# pressure_temp_uv.net
KiCad netlist of a schematic drawn in Altium Designer
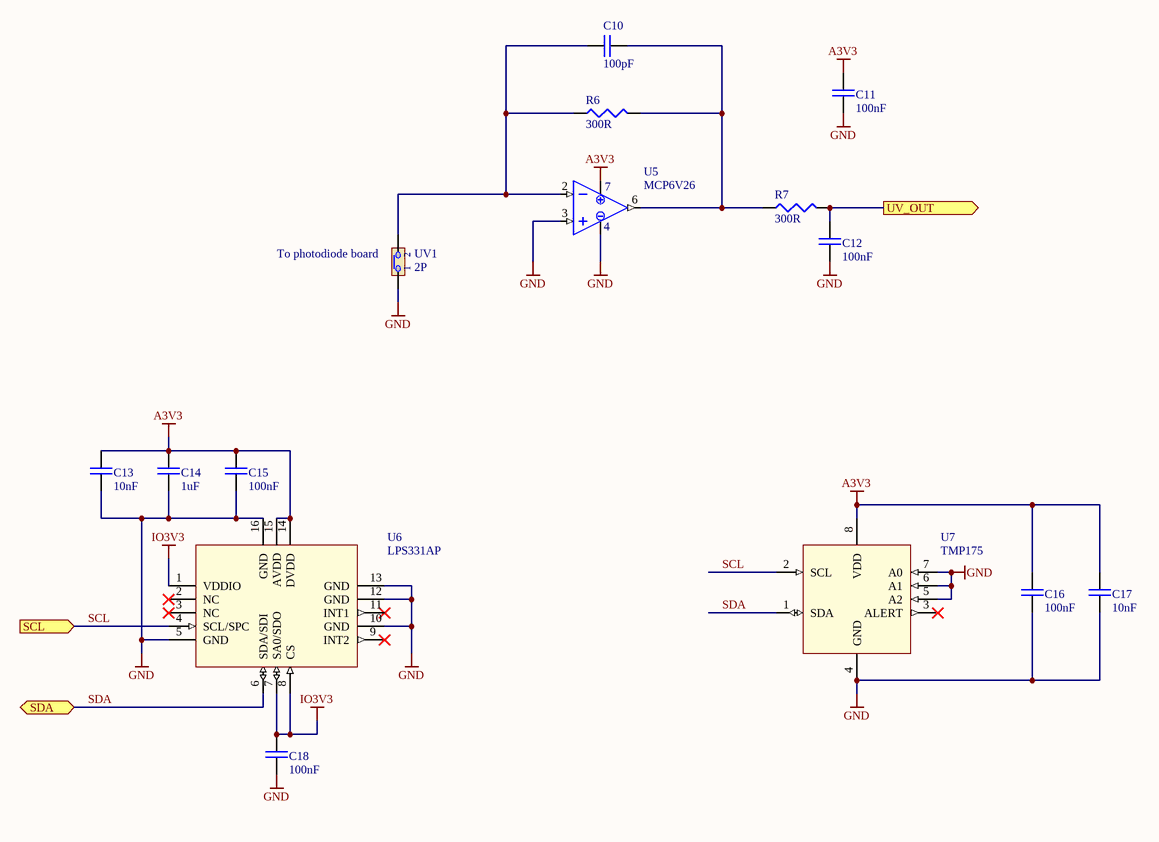
[diagram p0: pressure_temp_uv.SchDoc]

(export (version "E")
  (design (tool "Eeschema 10.0.6"))
  (components
    (comp (ref "C10")
      (value "100pF")
      (footprint "0603")
      (description "Capacitor")
      (fields (field (name "OWNER") "Nuno Brum"))
      (libsource (lib "Alcetronics_Devices") (part "CAP"))
    )
    (comp (ref "C11")
      (value "100nF")
      (footprint "0603")
      (description "Capacitor")
      (fields (field (name "OWNER") "Nuno Brum"))
      (libsource (lib "Alcetronics_Devices") (part "CAP"))
    )
    (comp (ref "C12")
      (value "100nF")
      (footprint "0603")
      (description "Capacitor")
      (fields (field (name "OWNER") "Nuno Brum"))
      (libsource (lib "Alcetronics_Devices") (part "CAP"))
    )
    (comp (ref "C13")
      (value "10nF")
      (footprint "0603")
      (description "Capacitor")
      (fields (field (name "OWNER") "Nuno Brum"))
      (libsource (lib "Alcetronics_Devices") (part "CAP"))
    )
    (comp (ref "C14")
      (value "1uF")
      (footprint "0603")
      (description "Capacitor")
      (fields (field (name "OWNER") "Nuno Brum"))
      (libsource (lib "Alcetronics_Devices") (part "CAP"))
    )
    (comp (ref "C15")
      (value "100nF")
      (footprint "0603")
      (description "Capacitor")
      (fields (field (name "OWNER") "Nuno Brum"))
      (libsource (lib "Alcetronics_Devices") (part "CAP"))
    )
    (comp (ref "C16")
      (value "100nF")
      (footprint "0603")
      (description "Capacitor")
      (fields (field (name "OWNER") "Nuno Brum"))
      (libsource (lib "Alcetronics_Devices") (part "CAP"))
    )
    (comp (ref "C17")
      (value "10nF")
      (footprint "0603")
      (description "Capacitor")
      (fields (field (name "OWNER") "Nuno Brum"))
      (libsource (lib "Alcetronics_Devices") (part "CAP"))
    )
    (comp (ref "C18")
      (value "100nF")
      (footprint "0603")
      (description "Capacitor")
      (fields (field (name "OWNER") "Nuno Brum"))
      (libsource (lib "Alcetronics_Devices") (part "CAP"))
    )
    (comp (ref "R6")
      (value "300R")
      (footprint "0603")
      (description "Resistor")
      (fields (field (name "OWNER") "Nuno Brum"))
      (libsource (lib "Alcetronics_Devices") (part "RES"))
    )
    (comp (ref "R7")
      (value "300R")
      (footprint "0603")
      (description "Resistor")
      (fields (field (name "OWNER") "Nuno Brum"))
      (libsource (lib "Alcetronics_Devices") (part "RES"))
    )
    (comp (ref "U5")
      (value "MCP6V26")
      (footprint "SOIC-8")
      (description "Low-Offset Opamp")
      (libsource (lib "Alcetronics_IC") (part "MCP6V26"))
    )
    (comp (ref "U6")
      (value "LPS331AP")
      (footprint "HCLGA-16")
      (description "Pressure sensor, 260 - 1260 mbar")
      (libsource (lib "Alcetronics_IC") (part "LPS331AP"))
    )
    (comp (ref "U7")
      (value "TMP175")
      (footprint "SOIC-8")
      (description "Digital Temperature Sensor")
      (libsource (lib "Alcetronics_IC") (part "TMP175"))
    )
    (comp (ref "UV1")
      (value "2P")
      (footprint "SIP-2")
      (description "2-pin Jumper")
      (fields (field (name "OWNER") "Nuno Brum"))
      (libsource (lib "Alcetronics_EM") (part "JMP2"))
    )
  )
  (nets
    (net (code "1") (name "/SCL") (class "Default")
      (node (ref "U6") (pin "4") (pinfunction "SCL/SPC_4") (pintype "input"))
      (node (ref "U7") (pin "2") (pinfunction "SCL_2") (pintype "input"))
    )
    (net (code "2") (name "/SDA") (class "Default")
      (node (ref "U6") (pin "6") (pinfunction "SDA/SDI_6") (pintype "bidirectional"))
      (node (ref "U7") (pin "1") (pinfunction "SDA_1") (pintype "bidirectional"))
    )
    (net (code "3") (name "/UV_OUT") (class "Default")
      (node (ref "C12") (pin "2") (pinfunction "2_2") (pintype "passive"))
      (node (ref "R7") (pin "2") (pinfunction "2_2") (pintype "passive"))
    )
    (net (code "4") (name "A3V3") (class "Default")
      (node (ref "C11") (pin "2") (pinfunction "2_2") (pintype "passive"))
      (node (ref "C13") (pin "2") (pinfunction "2_2") (pintype "passive"))
      (node (ref "C14") (pin "2") (pinfunction "2_2") (pintype "passive"))
      (node (ref "C15") (pin "2") (pinfunction "2_2") (pintype "passive"))
      (node (ref "C16") (pin "2") (pinfunction "2_2") (pintype "passive"))
      (node (ref "C17") (pin "2") (pinfunction "2_2") (pintype "passive"))
      (node (ref "U5") (pin "7") (pinfunction "VDD_7") (pintype "power_in"))
      (node (ref "U6") (pin "14") (pinfunction "DVDD_14") (pintype "power_in"))
      (node (ref "U6") (pin "15") (pinfunction "AVDD_15") (pintype "power_in"))
      (node (ref "U7") (pin "8") (pinfunction "VDD_8") (pintype "power_in"))
    )
    (net (code "5") (name "GND") (class "Default")
      (node (ref "C11") (pin "1") (pinfunction "1_1") (pintype "passive"))
      (node (ref "C12") (pin "1") (pinfunction "1_1") (pintype "passive"))
      (node (ref "C13") (pin "1") (pinfunction "1_1") (pintype "passive"))
      (node (ref "C14") (pin "1") (pinfunction "1_1") (pintype "passive"))
      (node (ref "C15") (pin "1") (pinfunction "1_1") (pintype "passive"))
      (node (ref "C16") (pin "1") (pinfunction "1_1") (pintype "passive"))
      (node (ref "C17") (pin "1") (pinfunction "1_1") (pintype "passive"))
      (node (ref "C18") (pin "1") (pinfunction "1_1") (pintype "passive"))
      (node (ref "U5") (pin "3") (pinfunction "INP_3") (pintype "input"))
      (node (ref "U5") (pin "4") (pinfunction "VSS_4") (pintype "power_in"))
      (node (ref "U6") (pin "10") (pinfunction "GND_10") (pintype "power_in"))
      (node (ref "U6") (pin "12") (pinfunction "GND_12") (pintype "power_in"))
      (node (ref "U6") (pin "13") (pinfunction "GND_13") (pintype "power_in"))
      (node (ref "U6") (pin "16") (pinfunction "GND_16") (pintype "power_in"))
      (node (ref "U6") (pin "5") (pinfunction "GND_5") (pintype "power_in"))
      (node (ref "U7") (pin "4") (pinfunction "GND_4") (pintype "power_in"))
      (node (ref "U7") (pin "5") (pinfunction "A2_5") (pintype "input"))
      (node (ref "U7") (pin "6") (pinfunction "A1_6") (pintype "input"))
      (node (ref "U7") (pin "7") (pinfunction "A0_7") (pintype "input"))
      (node (ref "UV1") (pin "1") (pinfunction "1_1") (pintype "passive"))
    )
    (net (code "6") (name "IO3V3") (class "Default")
      (node (ref "C18") (pin "2") (pinfunction "2_2") (pintype "passive"))
      (node (ref "U6") (pin "1") (pinfunction "VDDIO_1") (pintype "power_in"))
      (node (ref "U6") (pin "7") (pinfunction "SA0/SDO_7") (pintype "bidirectional"))
      (node (ref "U6") (pin "8") (pinfunction "CS_8") (pintype "input"))
    )
    (net (code "7") (name "Net-(U5-INN)") (class "Default")
      (node (ref "C10") (pin "1") (pinfunction "1_1") (pintype "passive"))
      (node (ref "R6") (pin "1") (pinfunction "1_1") (pintype "passive"))
      (node (ref "U5") (pin "2") (pinfunction "INN_2") (pintype "input"))
      (node (ref "UV1") (pin "2") (pinfunction "2_2") (pintype "passive"))
    )
    (net (code "8") (name "Net-(U5-VOUT)") (class "Default")
      (node (ref "C10") (pin "2") (pinfunction "2_2") (pintype "passive"))
      (node (ref "R6") (pin "2") (pinfunction "2_2") (pintype "passive"))
      (node (ref "R7") (pin "1") (pinfunction "1_1") (pintype "passive"))
      (node (ref "U5") (pin "6") (pinfunction "VOUT_6") (pintype "output"))
    )
    (net (code "9") (name "unconnected-(U6-INT1-Pad11)") (class "Default")
      (node (ref "U6") (pin "11") (pinfunction "INT1_11") (pintype "output+no_connect"))
    )
    (net (code "10") (name "unconnected-(U6-INT2-Pad9)") (class "Default")
      (node (ref "U6") (pin "9") (pinfunction "INT2_9") (pintype "output+no_connect"))
    )
    (net (code "11") (name "unconnected-(U6-NC-Pad2)") (class "Default")
      (node (ref "U6") (pin "2") (pinfunction "NC_2") (pintype "passive+no_connect"))
    )
    (net (code "12") (name "unconnected-(U6-NC-Pad3)") (class "Default")
      (node (ref "U6") (pin "3") (pinfunction "NC_3") (pintype "passive+no_connect"))
    )
    (net (code "13") (name "unconnected-(U7-ALERT-Pad3)") (class "Default")
      (node (ref "U7") (pin "3") (pinfunction "ALERT_3") (pintype "output+no_connect"))
    )
  )
)
